# debouncer.net
KiCad netlist of a schematic drawn in EAGLE
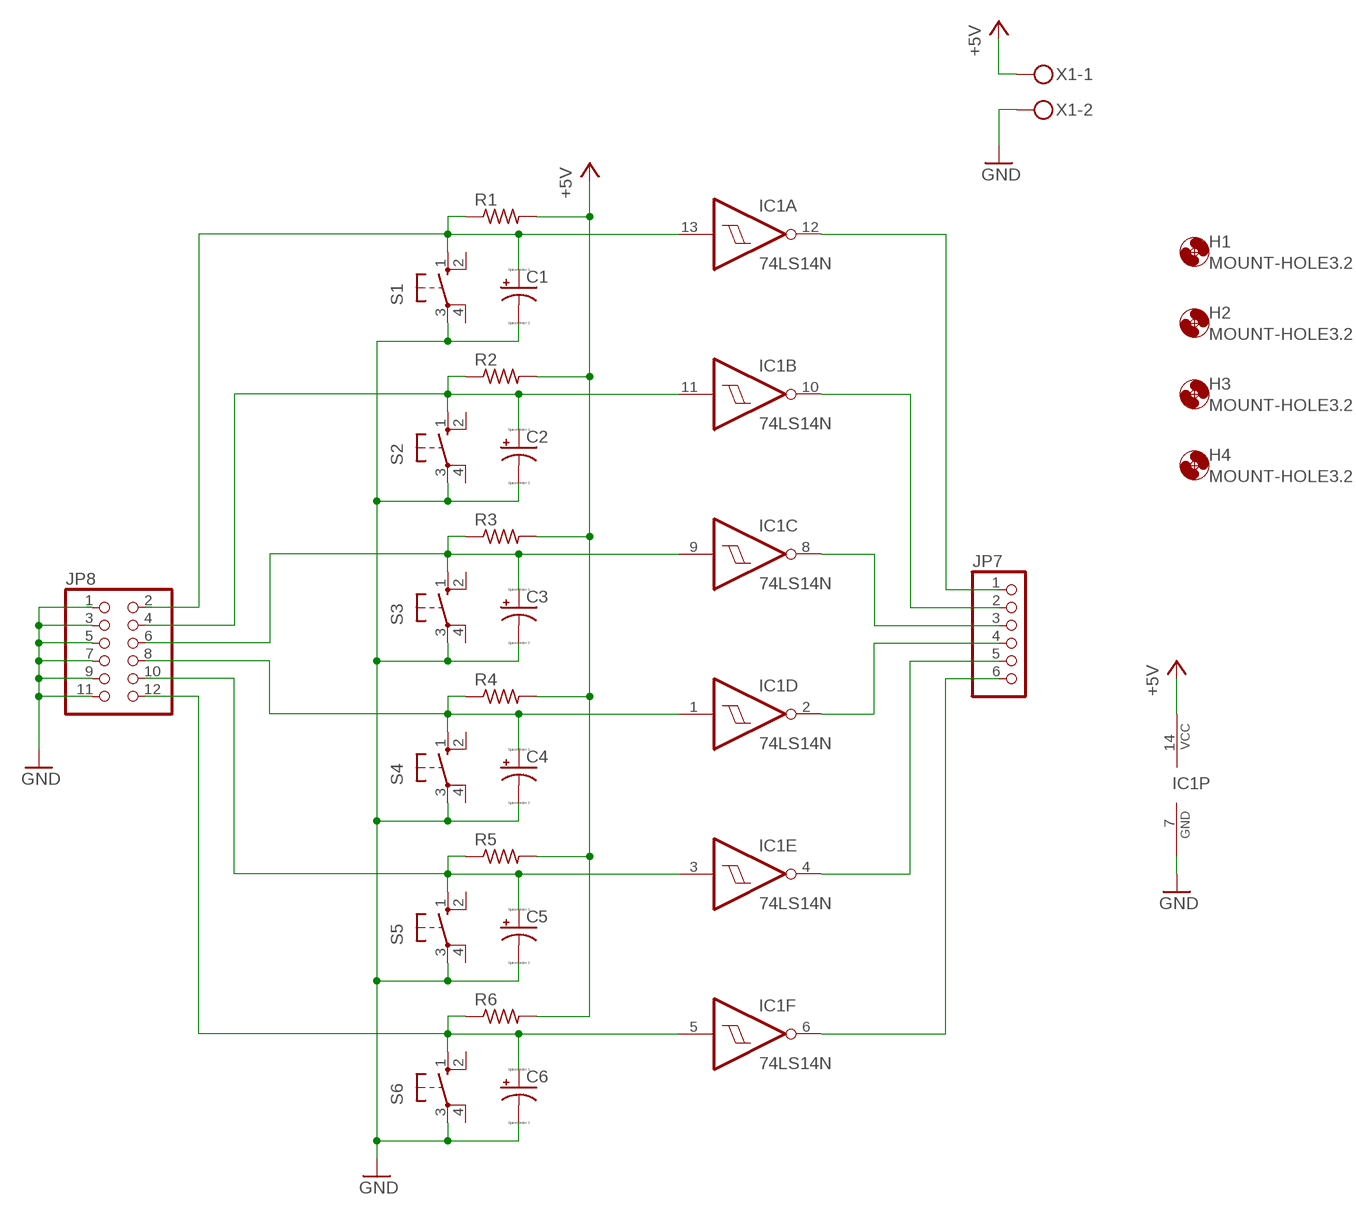
[diagram p0: schematic, sheet 1]

(export (version "E")
  (design (tool "Eeschema 10.0.6"))
  (components
    (comp (ref "C1")
      (value "CPOL-USE2-5")
      (footprint "eagle-import:E2-5")
      (libsource (lib "eagle-import") (part "CPOL-USE2-5"))
    )
    (comp (ref "C2")
      (value "CPOL-USE2-5")
      (footprint "eagle-import:E2-5")
      (libsource (lib "eagle-import") (part "CPOL-USE2-5"))
    )
    (comp (ref "C3")
      (value "CPOL-USE2-5")
      (footprint "eagle-import:E2-5")
      (libsource (lib "eagle-import") (part "CPOL-USE2-5"))
    )
    (comp (ref "C4")
      (value "CPOL-USE2-5")
      (footprint "eagle-import:E2-5")
      (libsource (lib "eagle-import") (part "CPOL-USE2-5"))
    )
    (comp (ref "C5")
      (value "CPOL-USE2-5")
      (footprint "eagle-import:E2-5")
      (libsource (lib "eagle-import") (part "CPOL-USE2-5"))
    )
    (comp (ref "C6")
      (value "CPOL-USE2-5")
      (footprint "eagle-import:E2-5")
      (libsource (lib "eagle-import") (part "CPOL-USE2-5"))
    )
    (comp (ref "H1")
      (value "MOUNT-HOLE3.2")
      (footprint "eagle-import:3,2")
      (libsource (lib "eagle-import") (part "MOUNT-HOLE3.2"))
    )
    (comp (ref "H2")
      (value "MOUNT-HOLE3.2")
      (footprint "eagle-import:3,2")
      (libsource (lib "eagle-import") (part "MOUNT-HOLE3.2"))
    )
    (comp (ref "H3")
      (value "MOUNT-HOLE3.2")
      (footprint "eagle-import:3,2")
      (libsource (lib "eagle-import") (part "MOUNT-HOLE3.2"))
    )
    (comp (ref "H4")
      (value "MOUNT-HOLE3.2")
      (footprint "eagle-import:3,2")
      (libsource (lib "eagle-import") (part "MOUNT-HOLE3.2"))
    )
    (comp (ref "IC1")
      (value "74LS14N")
      (footprint "eagle-import:DIL14")
      (libsource (lib "eagle-import") (part "7414NLS"))
    )
    (comp (ref "JP7")
      (value "PINHD-1X6")
      (footprint "eagle-import:1X06")
      (libsource (lib "eagle-import") (part "PINHD-1X6"))
    )
    (comp (ref "JP8")
      (value "PINHD-2X6")
      (footprint "eagle-import:2X06")
      (libsource (lib "eagle-import") (part "PINHD-2X6"))
    )
    (comp (ref "R1")
      (value "R-US_0207/12")
      (footprint "eagle-import:0207_12")
      (libsource (lib "eagle-import") (part "R-US_0207/12"))
    )
    (comp (ref "R2")
      (value "R-US_0207/12")
      (footprint "eagle-import:0207_12")
      (libsource (lib "eagle-import") (part "R-US_0207/12"))
    )
    (comp (ref "R3")
      (value "R-US_0207/12")
      (footprint "eagle-import:0207_12")
      (libsource (lib "eagle-import") (part "R-US_0207/12"))
    )
    (comp (ref "R4")
      (value "R-US_0207/12")
      (footprint "eagle-import:0207_12")
      (libsource (lib "eagle-import") (part "R-US_0207/12"))
    )
    (comp (ref "R5")
      (value "R-US_0207/12")
      (footprint "eagle-import:0207_12")
      (libsource (lib "eagle-import") (part "R-US_0207/12"))
    )
    (comp (ref "R6")
      (value "R-US_0207/12")
      (footprint "eagle-import:0207_12")
      (libsource (lib "eagle-import") (part "R-US_0207/12"))
    )
    (comp (ref "S1")
      (value "10-XX")
      (footprint "eagle-import:B3F-10XX")
      (fields (field (name "MPN") "B3F-1000"))
      (libsource (lib "eagle-import") (part "10-XX"))
    )
    (comp (ref "S2")
      (value "10-XX")
      (footprint "eagle-import:B3F-10XX")
      (fields (field (name "MPN") "B3F-1000"))
      (libsource (lib "eagle-import") (part "10-XX"))
    )
    (comp (ref "S3")
      (value "10-XX")
      (footprint "eagle-import:B3F-10XX")
      (fields (field (name "MPN") "B3F-1000"))
      (libsource (lib "eagle-import") (part "10-XX"))
    )
    (comp (ref "S4")
      (value "10-XX")
      (footprint "eagle-import:B3F-10XX")
      (fields (field (name "MPN") "B3F-1000"))
      (libsource (lib "eagle-import") (part "10-XX"))
    )
    (comp (ref "S5")
      (value "10-XX")
      (footprint "eagle-import:B3F-10XX")
      (fields (field (name "MPN") "B3F-1000"))
      (libsource (lib "eagle-import") (part "10-XX"))
    )
    (comp (ref "S6")
      (value "10-XX")
      (footprint "eagle-import:B3F-10XX")
      (fields (field (name "MPN") "B3F-1000"))
      (libsource (lib "eagle-import") (part "10-XX"))
    )
    (comp (ref "X1")
      (value "MKDSN1,5/2-5,08")
      (footprint "eagle-import:MKDSN1,5_2-5,08")
      (libsource (lib "eagle-import") (part "MKDSN1,5/2-5,08"))
    )
  )
  (nets
    (net (code "1") (name "+5V") (class "Default")
      (node (ref "IC1") (pin "14") (pinfunction "VCC_14") (pintype "power_in"))
      (node (ref "R1") (pin "2") (pinfunction "2_2") (pintype "passive"))
      (node (ref "R2") (pin "2") (pinfunction "2_2") (pintype "passive"))
      (node (ref "R3") (pin "2") (pinfunction "2_2") (pintype "passive"))
      (node (ref "R4") (pin "2") (pinfunction "2_2") (pintype "passive"))
      (node (ref "R5") (pin "2") (pinfunction "2_2") (pintype "passive"))
      (node (ref "R6") (pin "2") (pinfunction "2_2") (pintype "passive"))
      (node (ref "X1") (pin "1") (pinfunction "KL_1") (pintype "passive"))
    )
    (net (code "2") (name "GND") (class "Default")
      (node (ref "C1") (pin "-") (pinfunction "-_-") (pintype "passive"))
      (node (ref "C2") (pin "-") (pinfunction "-_-") (pintype "passive"))
      (node (ref "C3") (pin "-") (pinfunction "-_-") (pintype "passive"))
      (node (ref "C4") (pin "-") (pinfunction "-_-") (pintype "passive"))
      (node (ref "C5") (pin "-") (pinfunction "-_-") (pintype "passive"))
      (node (ref "C6") (pin "-") (pinfunction "-_-") (pintype "passive"))
      (node (ref "IC1") (pin "7") (pinfunction "GND_7") (pintype "power_in"))
      (node (ref "JP8") (pin "1") (pinfunction "1_1") (pintype "passive"))
      (node (ref "JP8") (pin "11") (pinfunction "11_11") (pintype "passive"))
      (node (ref "JP8") (pin "3") (pinfunction "3_3") (pintype "passive"))
      (node (ref "JP8") (pin "5") (pinfunction "5_5") (pintype "passive"))
      (node (ref "JP8") (pin "7") (pinfunction "7_7") (pintype "passive"))
      (node (ref "JP8") (pin "9") (pinfunction "9_9") (pintype "passive"))
      (node (ref "S1") (pin "3") (pinfunction "P_3") (pintype "passive"))
      (node (ref "S2") (pin "3") (pinfunction "P_3") (pintype "passive"))
      (node (ref "S3") (pin "3") (pinfunction "P_3") (pintype "passive"))
      (node (ref "S4") (pin "3") (pinfunction "P_3") (pintype "passive"))
      (node (ref "S5") (pin "3") (pinfunction "P_3") (pintype "passive"))
      (node (ref "S6") (pin "3") (pinfunction "P_3") (pintype "passive"))
      (node (ref "X1") (pin "2") (pinfunction "KL_2") (pintype "passive"))
    )
    (net (code "3") (name "Net-(IC1A-I)") (class "Default")
      (node (ref "C1") (pin "+") (pinfunction "+_+") (pintype "passive"))
      (node (ref "IC1") (pin "13") (pinfunction "I_13") (pintype "input"))
      (node (ref "JP8") (pin "2") (pinfunction "2_2") (pintype "passive"))
      (node (ref "R1") (pin "1") (pinfunction "1_1") (pintype "passive"))
      (node (ref "S1") (pin "1") (pinfunction "S_1") (pintype "passive"))
    )
    (net (code "4") (name "Net-(IC1A-O)") (class "Default")
      (node (ref "IC1") (pin "12") (pinfunction "O_12") (pintype "output"))
      (node (ref "JP7") (pin "1") (pinfunction "1_1") (pintype "passive"))
    )
    (net (code "5") (name "Net-(IC1B-I)") (class "Default")
      (node (ref "C2") (pin "+") (pinfunction "+_+") (pintype "passive"))
      (node (ref "IC1") (pin "11") (pinfunction "I_11") (pintype "input"))
      (node (ref "JP8") (pin "4") (pinfunction "4_4") (pintype "passive"))
      (node (ref "R2") (pin "1") (pinfunction "1_1") (pintype "passive"))
      (node (ref "S2") (pin "1") (pinfunction "S_1") (pintype "passive"))
    )
    (net (code "6") (name "Net-(IC1B-O)") (class "Default")
      (node (ref "IC1") (pin "10") (pinfunction "O_10") (pintype "output"))
      (node (ref "JP7") (pin "2") (pinfunction "2_2") (pintype "passive"))
    )
    (net (code "7") (name "Net-(IC1C-I)") (class "Default")
      (node (ref "C3") (pin "+") (pinfunction "+_+") (pintype "passive"))
      (node (ref "IC1") (pin "9") (pinfunction "I_9") (pintype "input"))
      (node (ref "JP8") (pin "6") (pinfunction "6_6") (pintype "passive"))
      (node (ref "R3") (pin "1") (pinfunction "1_1") (pintype "passive"))
      (node (ref "S3") (pin "1") (pinfunction "S_1") (pintype "passive"))
    )
    (net (code "8") (name "Net-(IC1C-O)") (class "Default")
      (node (ref "IC1") (pin "8") (pinfunction "O_8") (pintype "output"))
      (node (ref "JP7") (pin "3") (pinfunction "3_3") (pintype "passive"))
    )
    (net (code "9") (name "Net-(IC1D-I)") (class "Default")
      (node (ref "C4") (pin "+") (pinfunction "+_+") (pintype "passive"))
      (node (ref "IC1") (pin "1") (pinfunction "I_1") (pintype "input"))
      (node (ref "JP8") (pin "8") (pinfunction "8_8") (pintype "passive"))
      (node (ref "R4") (pin "1") (pinfunction "1_1") (pintype "passive"))
      (node (ref "S4") (pin "1") (pinfunction "S_1") (pintype "passive"))
    )
    (net (code "10") (name "Net-(IC1D-O)") (class "Default")
      (node (ref "IC1") (pin "2") (pinfunction "O_2") (pintype "output"))
      (node (ref "JP7") (pin "4") (pinfunction "4_4") (pintype "passive"))
    )
    (net (code "11") (name "Net-(IC1E-I)") (class "Default")
      (node (ref "C5") (pin "+") (pinfunction "+_+") (pintype "passive"))
      (node (ref "IC1") (pin "3") (pinfunction "I_3") (pintype "input"))
      (node (ref "JP8") (pin "10") (pinfunction "10_10") (pintype "passive"))
      (node (ref "R5") (pin "1") (pinfunction "1_1") (pintype "passive"))
      (node (ref "S5") (pin "1") (pinfunction "S_1") (pintype "passive"))
    )
    (net (code "12") (name "Net-(IC1E-O)") (class "Default")
      (node (ref "IC1") (pin "4") (pinfunction "O_4") (pintype "output"))
      (node (ref "JP7") (pin "5") (pinfunction "5_5") (pintype "passive"))
    )
    (net (code "13") (name "Net-(IC1F-I)") (class "Default")
      (node (ref "C6") (pin "+") (pinfunction "+_+") (pintype "passive"))
      (node (ref "IC1") (pin "5") (pinfunction "I_5") (pintype "input"))
      (node (ref "JP8") (pin "12") (pinfunction "12_12") (pintype "passive"))
      (node (ref "R6") (pin "1") (pinfunction "1_1") (pintype "passive"))
      (node (ref "S6") (pin "1") (pinfunction "S_1") (pintype "passive"))
    )
    (net (code "14") (name "Net-(IC1F-O)") (class "Default")
      (node (ref "IC1") (pin "6") (pinfunction "O_6") (pintype "output"))
      (node (ref "JP7") (pin "6") (pinfunction "6_6") (pintype "passive"))
    )
    (net (code "15") (name "unconnected-(S1-P1-Pad4)") (class "Default")
      (node (ref "S1") (pin "4") (pinfunction "P1_4") (pintype "passive"))
    )
    (net (code "16") (name "unconnected-(S1-S1-Pad2)") (class "Default")
      (node (ref "S1") (pin "2") (pinfunction "S1_2") (pintype "passive"))
    )
    (net (code "17") (name "unconnected-(S2-P1-Pad4)") (class "Default")
      (node (ref "S2") (pin "4") (pinfunction "P1_4") (pintype "passive"))
    )
    (net (code "18") (name "unconnected-(S2-S1-Pad2)") (class "Default")
      (node (ref "S2") (pin "2") (pinfunction "S1_2") (pintype "passive"))
    )
    (net (code "19") (name "unconnected-(S3-P1-Pad4)") (class "Default")
      (node (ref "S3") (pin "4") (pinfunction "P1_4") (pintype "passive"))
    )
    (net (code "20") (name "unconnected-(S3-S1-Pad2)") (class "Default")
      (node (ref "S3") (pin "2") (pinfunction "S1_2") (pintype "passive"))
    )
    (net (code "21") (name "unconnected-(S4-P1-Pad4)") (class "Default")
      (node (ref "S4") (pin "4") (pinfunction "P1_4") (pintype "passive"))
    )
    (net (code "22") (name "unconnected-(S4-S1-Pad2)") (class "Default")
      (node (ref "S4") (pin "2") (pinfunction "S1_2") (pintype "passive"))
    )
    (net (code "23") (name "unconnected-(S5-P1-Pad4)") (class "Default")
      (node (ref "S5") (pin "4") (pinfunction "P1_4") (pintype "passive"))
    )
    (net (code "24") (name "unconnected-(S5-S1-Pad2)") (class "Default")
      (node (ref "S5") (pin "2") (pinfunction "S1_2") (pintype "passive"))
    )
    (net (code "25") (name "unconnected-(S6-P1-Pad4)") (class "Default")
      (node (ref "S6") (pin "4") (pinfunction "P1_4") (pintype "passive"))
    )
    (net (code "26") (name "unconnected-(S6-S1-Pad2)") (class "Default")
      (node (ref "S6") (pin "2") (pinfunction "S1_2") (pintype "passive"))
    )
  )
)
